# Sematik.net
KiCad netlist of a schematic drawn in Altium Designer
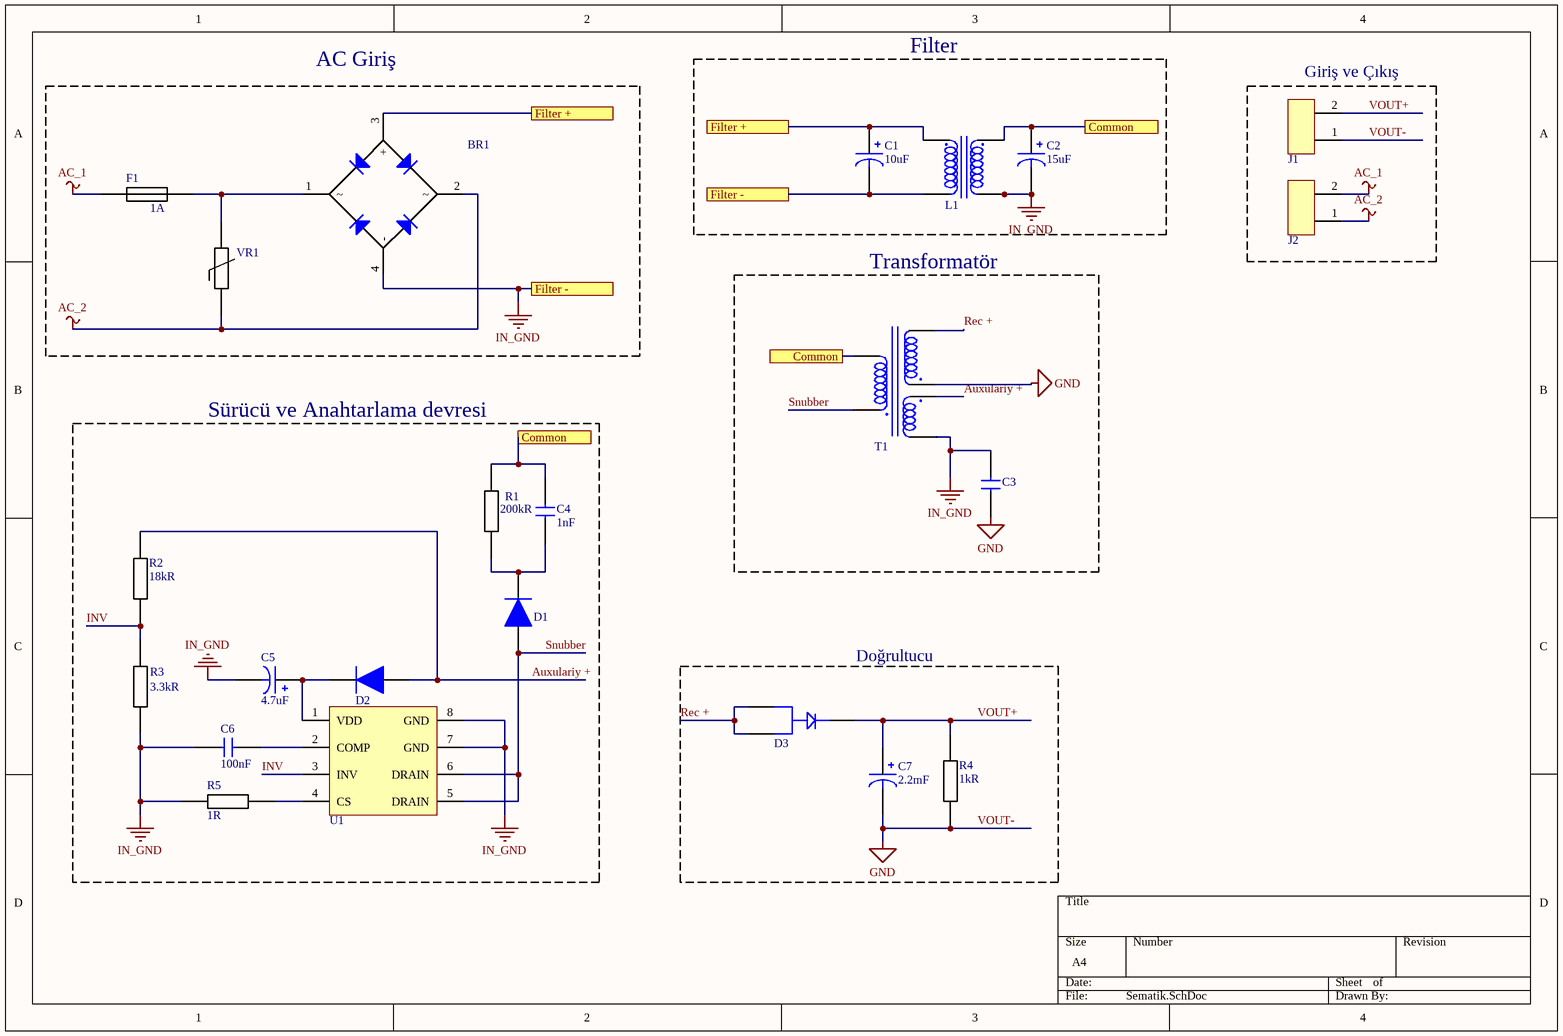
[diagram p0: Sematik.SchDoc]

(export (version "E")
  (design (tool "Eeschema 10.0.6"))
  (components
    (comp (ref "BR1")
      (value "DB105STR")
      (footprint "DB105STR")
      (description "Bridge Rect 1PHASE 600V 1A Db-s")
      (fields
        (field (name "MANUFACTURER") "Sangdest Microelectronics")
        (field (name "MANUFACTURER PART NUMBER") "DB105S")
        (field (name "DESIGNED BY") "Kerem")
      )
      (libsource (lib "SMPS") (part "DB105STR"))
    )
    (comp (ref "C1")
      (value "10uF")
      (footprint "CAP_ALU_10uF")
      (description "Aluminum Electrolytic Capacitor, Polarized, Aluminum (wet), 400V, 20% +Tol, 20% -Tol, 10uF")
      (fields
        (field (name "MANUFACTURER") "Nichicon")
        (field (name "MANUFACTURER PART NUMBER") "UCY2G100MPD1TD")
      )
      (libsource (lib "SMPS") (part "CAP_ALU_10uF"))
    )
    (comp (ref "C2")
      (value "15uF")
      (footprint "CAP_ALU_15uF")
      (description "Aluminum Electrolytic Capacitor, Polarized, Aluminum (wet), 400V, 20% +Tol, 20% -Tol, 15uF")
      (fields
        (field (name "MANUFACTURER") "Nichicon")
        (field (name "MANUFACTURER PART NUMBER") "UCY2G150MPD")
      )
      (libsource (lib "SMPS") (part "CAP_ALU_15uF"))
    )
    (comp (ref "C3")
      (value "DE2E3SA102MN3AT02F")
      (footprint "CAP_CER_1000pF_250V_RADİAL")
      (description "Ceramic Capacitor, Ceramic, 20% +Tol, 20% -Tol, E, -55/+20% TC, 0.001uF, Through Hole Mount")
      (fields (field (name "MANUFACTURER") "Murata"))
      (libsource (lib "SMPS") (part "CAP_CER_1000pF_250V_RADİAL"))
    )
    (comp (ref "C4")
      (value "1nF")
      (footprint "CAP_1206")
      (fields
        (field (name "MANUFACTURER") "KEMET")
        (field (name "MANUFACTURER PART NUMBER") "C1206C102KDRACTU")
      )
      (libsource (lib "SMPS") (part "CAP_CER_1nF_1206"))
    )
    (comp (ref "C5")
      (value "4.7uF")
      (footprint "CAP_ALU_4.7uF")
      (description "Aluminum Electrolytic Capacitor, Aluminum (wet)")
      (fields
        (field (name "MANUFACTURER") "Wurth Electronics")
        (field (name "MANUFACTURER PART NUMBER") "860010672008")
      )
      (libsource (lib "SMPS") (part "CAP_ALU_4.7uF"))
    )
    (comp (ref "C6")
      (value "100nF")
      (footprint "CAP_0805")
      (description "Ceramic Capacitor,50V, %10, 0.1uF, Surface Mount, 0805")
      (fields
        (field (name "MANUFACTURER") "Samsung")
        (field (name "MANUFACTURER PART NUMBER") "CL21B104KBCNNNC")
        (field (name "DESIGNED BY") "Kerem")
      )
      (libsource (lib "SMPS") (part "CAP_CER_0.1uF_0805"))
    )
    (comp (ref "C7")
      (value "2.2mF")
      (footprint "CAP_ALU_2200uF")
      (fields
        (field (name "MANUFACTURER") "Panasonic")
        (field (name "MANUFACTURER PART NUMBER") "ECA-1AM222")
      )
      (libsource (lib "SMPS") (part "CAP_ALU_2200uF"))
    )
    (comp (ref "D1")
      (value "1N4007G-T")
      (footprint "1N4007G-T Diode")
      (description "Rectifier Diode, 1 Phase, 1 Element, 1A, 1000V V(RRM), Silicon, DO-41")
      (fields (field (name "MANUFACTURER") "Diodes"))
      (libsource (lib "SMPS") (part "1N4007G-T Diode"))
    )
    (comp (ref "D2")
      (value "1N4007G-T")
      (footprint "1N4007G-T Diode")
      (description "Rectifier Diode, 1 Phase, 1 Element, 1A, 1000V V(RRM), Silicon, DO-41")
      (fields (field (name "MANUFACTURER") "Diodes"))
      (libsource (lib "SMPS") (part "1N4007G-T Diode"))
    )
    (comp (ref "D3")
      (value "SS10P4-M3/86A SCHOTTKY DİODE")
      (footprint "SS10P4-M3/86A")
      (description "Rectifier Diode, Schottky, 1 Phase, 1 Element, 10A, 40V V(RRM), Silicon, TO-277A")
      (fields
        (field (name "MANUFACTURER") "Vishay Semiconductors")
        (field (name "MANUFACTURER PART NUMBER") "SS10P4-M3/86A")
      )
      (libsource (lib "SMPS") (part "SS10P4-M3/86A"))
    )
    (comp (ref "F1")
      (value "05200101Z")
      (footprint "05200101Z Fuse Block")
      (description "Fuses/Accessories")
      (fields (field (name "MANUFACTURER") "Littelfuse") (field (name "AMPER") "1A"))
      (libsource (lib "SMPS") (part "05200101Z Fuse Block"))
    )
    (comp (ref "J1")
      (value "JACK")
      (footprint "TBP01R1-508")
      (description "Strip Terminal Block 2 Pins")
      (fields
        (field (name "MANUFACTURER") "CUI Devices")
        (field (name "MANUFACTURER PART NUMBER") "TBP01R1-508-02BE")
        (field (name "DESIGNED BY") "Kerem")
      )
      (libsource (lib "SMPS") (part "TBP01R1-508-02BE"))
    )
    (comp (ref "J2")
      (value "JACK")
      (footprint "TBP01R1-508")
      (description "Strip Terminal Block 2 Pins")
      (fields
        (field (name "MANUFACTURER") "CUI Devices")
        (field (name "MANUFACTURER PART NUMBER") "TBP01R1-508-02BE")
        (field (name "DESIGNED BY") "Kerem")
      )
      (libsource (lib "library") (part "TBP01R1-508-02BE"))
    )
    (comp (ref "L1")
      (value "LFU09V-102(0.35MM)")
      (footprint "Line Filter Choke Common Mode")
      (libsource (lib "SMPS") (part "Line Filter Choke Common Mode"))
    )
    (comp (ref "R1")
      (value "200kR")
      (footprint "RES-1206")
      (fields
        (field (name "MANUFACTURER") "Yageo")
        (field (name "MANUFACTURER PART NUMBER") "RC1206JR-07200KL")
        (field (name "TOLERANCE") "5%")
      )
      (libsource (lib "SMPS") (part "RES_200K OHM_1206"))
    )
    (comp (ref "R2")
      (value "18kR")
      (footprint "RES_0805")
      (fields
        (field (name "MANUFACTURER") "Stackpole Electronics")
        (field (name "MANUFACTURER PART NUMBER") "RMCF0805FT18K0")
        (field (name "TOLERANCE") "1%")
      )
      (libsource (lib "SMPS") (part "RES_18K OHM_0805"))
    )
    (comp (ref "R3")
      (value "3.3kR")
      (footprint "RES_0805")
      (description "3.3 kOhms ±1% 0.25W, 1/4W Chip Resistor 0805 (2012 Metric) Moisture Resistant Thick Film")
      (fields
        (field (name "MANUFACTURER") "Yageo")
        (field (name "MANUFACTURER PART NUMBER") "RC0805FR-7W3K3L")
      )
      (libsource (lib "SMPS") (part "RES_3K3 OHM_0805"))
    )
    (comp (ref "R4")
      (value "1kR")
      (footprint "RES-1206")
      (fields
        (field (name "MANUFACTURER") "Yageo")
        (field (name "MANUFACTURER PART NUMBER") "RC1206JR-071KL")
        (field (name "TOLERANCE") "5%")
      )
      (libsource (lib "SMPS") (part "RES_1K OHM_1206"))
    )
    (comp (ref "R5")
      (value "1R")
      (footprint "RES-1206")
      (fields
        (field (name "MANUFACTURER") "Yageo")
        (field (name "MANUFACTURER PART NUMBER") "RC1206JR-071RL")
        (field (name "TOLERANCE") "5%")
      )
      (libsource (lib "SMPS") (part "RES_1 OHM_1206"))
    )
    (comp (ref "T1")
      (value "750341599")
      (footprint "SMPS TRAFO")
      (description "SMPS Transformer")
      (fields (field (name "MANUFACTURER") "Wurth Electronics Midcom"))
      (libsource (lib "SMPS") (part "EE-22 SMPS_TRAFO"))
    )
    (comp (ref "U1") (value "UCSR3652SG") (footprint "sop-8") (libsource (lib "SMPS") (part "UCSR3652SG")))
    (comp (ref "VR1")
      (value "820513011")
      (footprint "820513011 Varistor")
      (description "Varistor, 385V, 70J, Through Hole Mount")
      (fields (field (name "MANUFACTURER") "Wurth Electronics") (field (name "POWER") "400mW"))
      (libsource (lib "SMPS") (part "820513011 Varistor"))
    )
  )
  (nets
    (net (code "1") (name "/Auxulariy +") (class "Default")
      (node (ref "D2") (pin "2") (pinfunction "2_2") (pintype "passive"))
      (node (ref "R2") (pin "2") (pinfunction "2_2") (pintype "passive"))
      (node (ref "T1") (pin "5") (pinfunction "5_5") (pintype "passive"))
    )
    (net (code "2") (name "/Common") (class "Default")
      (node (ref "C2") (pin "1") (pinfunction "1_1") (pintype "passive"))
      (node (ref "C4") (pin "2") (pinfunction "2_2") (pintype "passive"))
      (node (ref "L1") (pin "4") (pinfunction "4_4") (pintype "passive"))
      (node (ref "R1") (pin "2") (pinfunction "2_2") (pintype "passive"))
      (node (ref "T1") (pin "1") (pinfunction "1_1") (pintype "passive"))
    )
    (net (code "3") (name "/Filter +") (class "Default")
      (node (ref "BR1") (pin "3") (pinfunction "+_3") (pintype "passive"))
      (node (ref "C1") (pin "1") (pinfunction "1_1") (pintype "passive"))
      (node (ref "L1") (pin "1") (pinfunction "1_1") (pintype "passive"))
    )
    (net (code "4") (name "/INV") (class "Default")
      (node (ref "R2") (pin "1") (pinfunction "1_1") (pintype "passive"))
      (node (ref "R3") (pin "2") (pinfunction "2_2") (pintype "passive"))
      (node (ref "U1") (pin "3") (pinfunction "INV_3") (pintype "passive"))
    )
    (net (code "5") (name "/Rec +") (class "Default")
      (node (ref "D3") (pin "1") (pinfunction "ANOT_1_1") (pintype "passive"))
      (node (ref "D3") (pin "2") (pinfunction "ANOT_2_2") (pintype "passive"))
      (node (ref "T1") (pin "8") (pinfunction "8_8") (pintype "passive"))
    )
    (net (code "6") (name "/Snubber") (class "Default")
      (node (ref "D1") (pin "2") (pinfunction "2_2") (pintype "passive"))
      (node (ref "T1") (pin "2") (pinfunction "2_2") (pintype "passive"))
      (node (ref "U1") (pin "5") (pinfunction "DRAIN_5") (pintype "passive"))
      (node (ref "U1") (pin "6") (pinfunction "DRAIN_6") (pintype "passive"))
    )
    (net (code "7") (name "/VOUT+") (class "Default")
      (node (ref "C7") (pin "1") (pinfunction "1_1") (pintype "passive"))
      (node (ref "D3") (pin "K") (pinfunction "KATOT_K") (pintype "passive"))
      (node (ref "J1") (pin "2") (pinfunction "2_2") (pintype "power_in"))
      (node (ref "R4") (pin "2") (pinfunction "2_2") (pintype "passive"))
    )
    (net (code "8") (name "AC_1") (class "Default")
      (node (ref "F1") (pin "2") (pinfunction "2_2") (pintype "passive"))
      (node (ref "J2") (pin "2") (pinfunction "2_2") (pintype "power_in"))
    )
    (net (code "9") (name "AC_2") (class "Default")
      (node (ref "BR1") (pin "2") (pinfunction "~_2") (pintype "passive"))
      (node (ref "J2") (pin "1") (pinfunction "1_1") (pintype "power_in"))
      (node (ref "VR1") (pin "2") (pinfunction "2_2") (pintype "passive"))
    )
    (net (code "10") (name "GND") (class "Default")
      (node (ref "C3") (pin "1") (pinfunction "1_1") (pintype "passive"))
      (node (ref "C7") (pin "2") (pinfunction "2_2") (pintype "passive"))
      (node (ref "J1") (pin "1") (pinfunction "1_1") (pintype "power_in"))
      (node (ref "R4") (pin "1") (pinfunction "1_1") (pintype "passive"))
      (node (ref "T1") (pin "7") (pinfunction "7_7") (pintype "passive"))
    )
    (net (code "11") (name "IN_GND") (class "Default")
      (node (ref "BR1") (pin "4") (pinfunction "-_4") (pintype "passive"))
      (node (ref "C1") (pin "2") (pinfunction "2_2") (pintype "passive"))
      (node (ref "C2") (pin "2") (pinfunction "2_2") (pintype "passive"))
      (node (ref "C3") (pin "2") (pinfunction "2_2") (pintype "passive"))
      (node (ref "C5") (pin "2") (pinfunction "2_2") (pintype "passive"))
      (node (ref "C6") (pin "2") (pinfunction "2_2") (pintype "passive"))
      (node (ref "L1") (pin "2") (pinfunction "2_2") (pintype "passive"))
      (node (ref "L1") (pin "3") (pinfunction "3_3") (pintype "passive"))
      (node (ref "R3") (pin "1") (pinfunction "1_1") (pintype "passive"))
      (node (ref "R5") (pin "2") (pinfunction "2_2") (pintype "passive"))
      (node (ref "T1") (pin "4") (pinfunction "4_4") (pintype "passive"))
      (node (ref "U1") (pin "7") (pinfunction "GND_7") (pintype "passive"))
      (node (ref "U1") (pin "8") (pinfunction "GND_8") (pintype "passive"))
    )
    (net (code "12") (name "Net-(BR1-~-Pad1)") (class "Default")
      (node (ref "BR1") (pin "1") (pinfunction "~_1") (pintype "passive"))
      (node (ref "F1") (pin "1") (pinfunction "1_1") (pintype "passive"))
      (node (ref "VR1") (pin "1") (pinfunction "1_1") (pintype "passive"))
    )
    (net (code "13") (name "Net-(C4-Pad1)") (class "Default")
      (node (ref "C4") (pin "1") (pinfunction "1_1") (pintype "passive"))
      (node (ref "D1") (pin "1") (pinfunction "1_1") (pintype "passive"))
      (node (ref "R1") (pin "1") (pinfunction "1_1") (pintype "passive"))
    )
    (net (code "14") (name "Net-(U1-COMP)") (class "Default")
      (node (ref "C6") (pin "1") (pinfunction "1_1") (pintype "passive"))
      (node (ref "U1") (pin "2") (pinfunction "COMP_2") (pintype "passive"))
    )
    (net (code "15") (name "Net-(U1-CS)") (class "Default")
      (node (ref "R5") (pin "1") (pinfunction "1_1") (pintype "passive"))
      (node (ref "U1") (pin "4") (pinfunction "CS_4") (pintype "passive"))
    )
    (net (code "16") (name "Net-(U1-VDD)") (class "Default")
      (node (ref "C5") (pin "1") (pinfunction "1_1") (pintype "passive"))
      (node (ref "D2") (pin "1") (pinfunction "1_1") (pintype "passive"))
      (node (ref "U1") (pin "1") (pinfunction "VDD_1") (pintype "passive"))
    )
  )
)
